# G431.net
KiCad netlist of a schematic drawn in Altium Designer
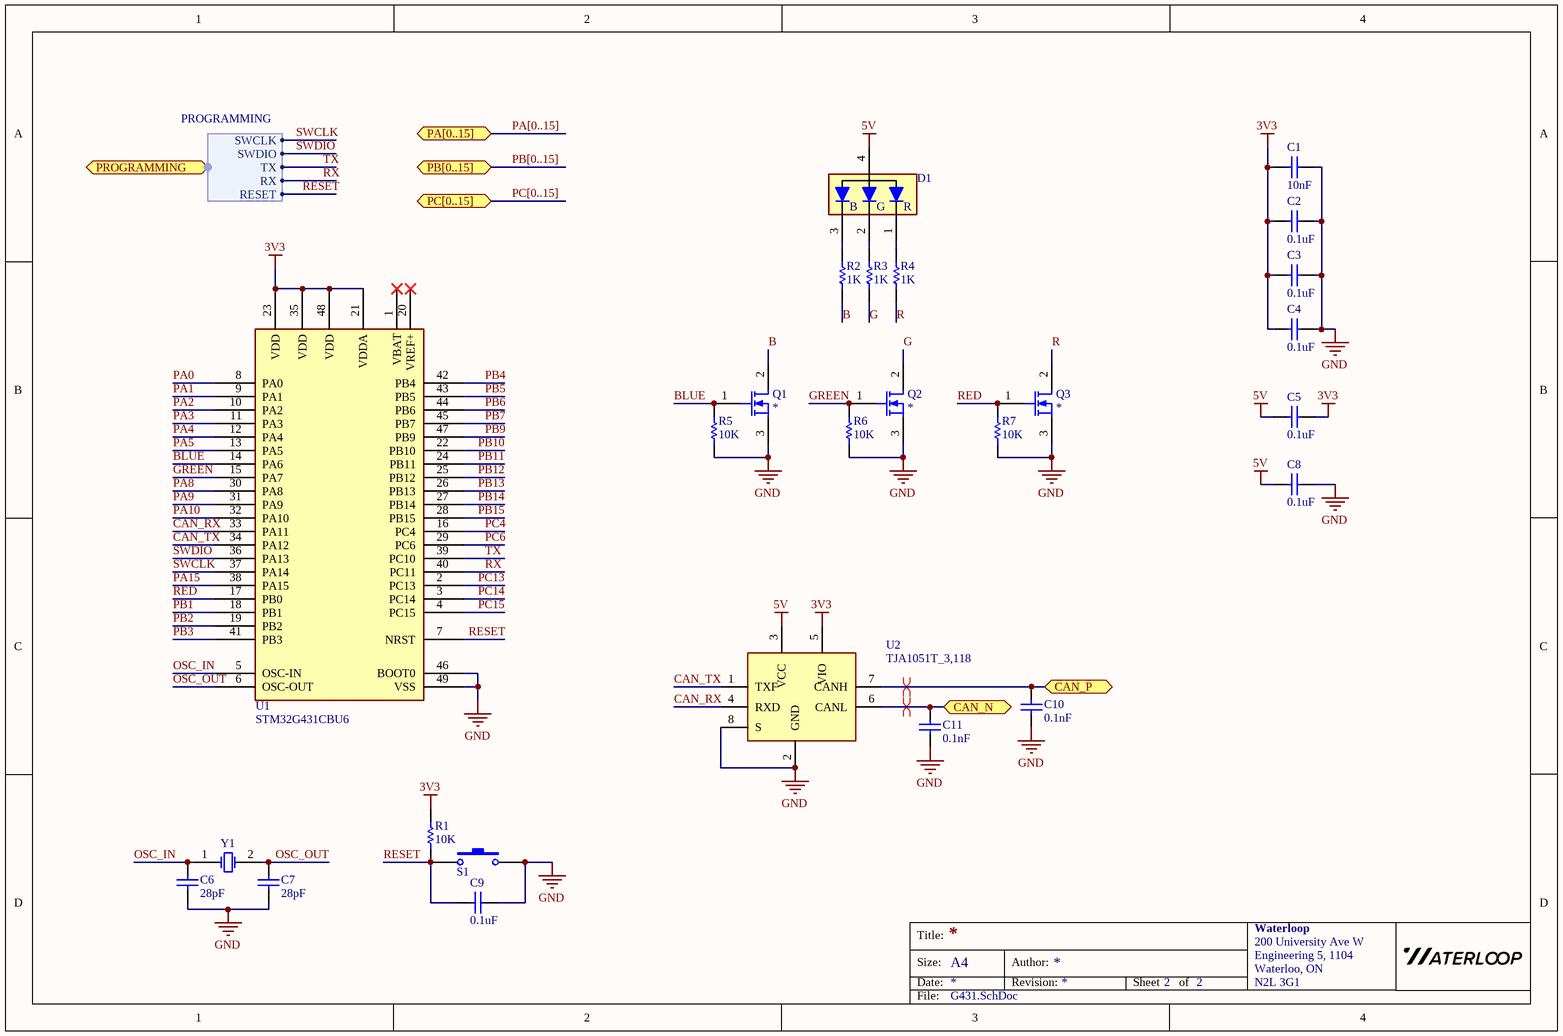
[diagram p0: G431.SchDoc]

(export (version "E")
  (design (tool "Eeschema 10.0.6"))
  (components
    (comp (ref "C1")
      (value "10nF")
      (footprint "0805 - Capacitor")
      (description "Nonpolarized Capacitor")
      (fields (field (name "Comment") "Capacitor - Nonpolarized"))
      (libsource (lib "General") (part "Capacitor - Nonpolarized"))
    )
    (comp (ref "C2")
      (value "0.1uF")
      (footprint "0805 - Capacitor")
      (description "Nonpolarized Capacitor")
      (fields (field (name "Comment") "Capacitor - Nonpolarized"))
      (libsource (lib "General") (part "Capacitor - Nonpolarized"))
    )
    (comp (ref "C3")
      (value "0.1uF")
      (footprint "0805 - Capacitor")
      (description "Nonpolarized Capacitor")
      (fields (field (name "Comment") "Capacitor - Nonpolarized"))
      (libsource (lib "General") (part "Capacitor - Nonpolarized"))
    )
    (comp (ref "C4")
      (value "0.1uF")
      (footprint "0805 - Capacitor")
      (description "Nonpolarized Capacitor")
      (fields (field (name "Comment") "Capacitor - Nonpolarized"))
      (libsource (lib "General") (part "Capacitor - Nonpolarized"))
    )
    (comp (ref "C5")
      (value "0.1uF")
      (footprint "0805 - Capacitor")
      (description "Nonpolarized Capacitor")
      (fields (field (name "Comment") "Capacitor - Nonpolarized"))
      (libsource (lib "General") (part "Capacitor - Nonpolarized"))
    )
    (comp (ref "C6")
      (value "28pF")
      (footprint "0805 - Capacitor")
      (description "Nonpolarized Capacitor")
      (fields (field (name "Comment") "Capacitor - Nonpolarized"))
      (libsource (lib "General") (part "Capacitor - Nonpolarized"))
    )
    (comp (ref "C7")
      (value "28pF")
      (footprint "0805 - Capacitor")
      (description "Nonpolarized Capacitor")
      (fields (field (name "Comment") "Capacitor - Nonpolarized"))
      (libsource (lib "General") (part "Capacitor - Nonpolarized"))
    )
    (comp (ref "C8")
      (value "0.1uF")
      (footprint "0805 - Capacitor")
      (description "Nonpolarized Capacitor")
      (fields (field (name "Comment") "Capacitor - Nonpolarized"))
      (libsource (lib "General") (part "Capacitor - Nonpolarized"))
    )
    (comp (ref "C9")
      (value "0.1uF")
      (footprint "0805 - Capacitor")
      (description "Nonpolarized Capacitor")
      (fields (field (name "Comment") "Capacitor - Nonpolarized"))
      (libsource (lib "General") (part "Capacitor - Nonpolarized"))
    )
    (comp (ref "C10")
      (value "0.1nF")
      (footprint "0805 - Capacitor")
      (description "Nonpolarized Capacitor")
      (fields (field (name "Comment") "Capacitor - Nonpolarized"))
      (libsource (lib "General") (part "Capacitor - Nonpolarized"))
    )
    (comp (ref "C11")
      (value "0.1nF")
      (footprint "0805 - Capacitor")
      (description "Nonpolarized Capacitor")
      (fields (field (name "Comment") "Capacitor - Nonpolarized"))
      (libsource (lib "General") (part "Capacitor - Nonpolarized"))
    )
    (comp (ref "D1")
      (value "RGB LED- Common Anode")
      (footprint "4-PLCC RGB LED")
      (libsource (lib "General") (part "RGB LED- Common Anode"))
    )
    (comp (ref "Q1")
      (value "MOSFET-N")
      (footprint "SC70/SOT323")
      (description "N-Channel MOSFET")
      (fields (field (name "ALTIUM_VALUE") "*"))
      (libsource (lib "General") (part "MOSFET-N"))
    )
    (comp (ref "Q2")
      (value "MOSFET-N")
      (footprint "SC70/SOT323")
      (description "N-Channel MOSFET")
      (fields (field (name "ALTIUM_VALUE") "*"))
      (libsource (lib "General") (part "MOSFET-N"))
    )
    (comp (ref "Q3")
      (value "MOSFET-N")
      (footprint "SC70/SOT323")
      (description "N-Channel MOSFET")
      (fields (field (name "ALTIUM_VALUE") "*"))
      (libsource (lib "General") (part "MOSFET-N"))
    )
    (comp (ref "R1")
      (value "10K")
      (footprint "0603 - Resistor")
      (description "Resistor")
      (libsource (lib "General") (part "Resistor"))
    )
    (comp (ref "R2")
      (value "1K")
      (footprint "0603 - Resistor")
      (description "Resistor")
      (libsource (lib "General") (part "Resistor"))
    )
    (comp (ref "R3")
      (value "1K")
      (footprint "0603 - Resistor")
      (description "Resistor")
      (libsource (lib "General") (part "Resistor"))
    )
    (comp (ref "R4")
      (value "1K")
      (footprint "0603 - Resistor")
      (description "Resistor")
      (libsource (lib "General") (part "Resistor"))
    )
    (comp (ref "R5")
      (value "10K")
      (footprint "0603 - Resistor")
      (description "Resistor")
      (libsource (lib "General") (part "Resistor"))
    )
    (comp (ref "R6")
      (value "10K")
      (footprint "0603 - Resistor")
      (description "Resistor")
      (libsource (lib "General") (part "Resistor"))
    )
    (comp (ref "R7")
      (value "10K")
      (footprint "0603 - Resistor")
      (description "Resistor")
      (libsource (lib "General") (part "Resistor"))
    )
    (comp (ref "S1")
      (value "Switch - Push Button")
      (footprint "6x6mm Switch")
      (description "Push Button Switch")
      (libsource (lib "General") (part "Switch - Push Button"))
    )
    (comp (ref "U1")
      (value "STM32G431CBU6")
      (footprint "STM32G431CBU6")
      (description "128K FLASH + 32K RAM MICRO")
      (fields (field (name "MANUFACTURER") "ST"))
      (libsource (lib "GeneralComponents") (part "STM32G431CBU6"))
    )
    (comp (ref "U2")
      (value "TJA1051T_3,118")
      (footprint "TJA1051T/3,118")
      (description "CAN Transceiver IC 4.5V-5.5V 250ns")
      (fields (field (name "MANUFACTURER") "NXP") (field (name "MANUFACTURER PART NUMBER") "TJA1051T/3,118"))
      (libsource (lib "GeneralComponents") (part "TJA1051T_3,118"))
    )
    (comp (ref "Y1")
      (value "Oscillator")
      (footprint "2-SMD NO LEAD CRSYSTAL")
      (description "Crystal Oscillator")
      (libsource (lib "General") (part "Oscillator"))
    )
  )
  (nets
    (net (code "21") (name "/B") (class "Default")
      (node (ref "Q1") (pin "2") (pinfunction "D_2") (pintype "passive"))
      (node (ref "R2") (pin "1") (pinfunction "1_1") (pintype "passive"))
    )
    (net (code "22") (name "/BLUE") (class "Default")
      (node (ref "Q1") (pin "1") (pinfunction "G_1") (pintype "passive"))
      (node (ref "R5") (pin "2") (pinfunction "2_2") (pintype "passive"))
      (node (ref "U1") (pin "14") (pinfunction "PA6_14") (pintype "passive"))
    )
    (net (code "23") (name "/CAN_N") (class "Default")
      (node (ref "C11") (pin "2") (pinfunction "2_2") (pintype "passive"))
      (node (ref "U2") (pin "6") (pinfunction "CANL_6") (pintype "passive"))
    )
    (net (code "24") (name "/CAN_P") (class "Default")
      (node (ref "C10") (pin "2") (pinfunction "2_2") (pintype "passive"))
      (node (ref "U2") (pin "7") (pinfunction "CANH_7") (pintype "passive"))
    )
    (net (code "25") (name "/CAN_RX") (class "Default")
      (node (ref "U1") (pin "33") (pinfunction "PA11_33") (pintype "passive"))
      (node (ref "U2") (pin "4") (pinfunction "RXD_4") (pintype "passive"))
    )
    (net (code "26") (name "/CAN_TX") (class "Default")
      (node (ref "U1") (pin "34") (pinfunction "PA12_34") (pintype "passive"))
      (node (ref "U2") (pin "1") (pinfunction "TXF_1") (pintype "passive"))
    )
    (net (code "27") (name "/G") (class "Default")
      (node (ref "Q2") (pin "2") (pinfunction "D_2") (pintype "passive"))
      (node (ref "R3") (pin "1") (pinfunction "1_1") (pintype "passive"))
    )
    (net (code "28") (name "/GREEN") (class "Default")
      (node (ref "Q2") (pin "1") (pinfunction "G_1") (pintype "passive"))
      (node (ref "R6") (pin "2") (pinfunction "2_2") (pintype "passive"))
      (node (ref "U1") (pin "15") (pinfunction "PA7_15") (pintype "passive"))
    )
    (net (code "29") (name "/OSC_IN") (class "Default")
      (node (ref "C6") (pin "2") (pinfunction "2_2") (pintype "passive"))
      (node (ref "U1") (pin "5") (pinfunction "OSC-IN_5") (pintype "passive"))
      (node (ref "Y1") (pin "1") (pinfunction "OSC1_1") (pintype "passive"))
    )
    (net (code "30") (name "/OSC_OUT") (class "Default")
      (node (ref "C7") (pin "2") (pinfunction "2_2") (pintype "passive"))
      (node (ref "U1") (pin "6") (pinfunction "OSC-OUT_6") (pintype "passive"))
      (node (ref "Y1") (pin "2") (pinfunction "OSC2_2") (pintype "passive"))
    )
    (net (code "31") (name "/PA0") (class "Default")
      (node (ref "U1") (pin "8") (pinfunction "PA0_8") (pintype "passive"))
    )
    (net (code "32") (name "/PA1") (class "Default")
      (node (ref "U1") (pin "9") (pinfunction "PA1_9") (pintype "passive"))
    )
    (net (code "33") (name "/PA2") (class "Default")
      (node (ref "U1") (pin "10") (pinfunction "PA2_10") (pintype "passive"))
    )
    (net (code "34") (name "/PA3") (class "Default")
      (node (ref "U1") (pin "11") (pinfunction "PA3_11") (pintype "passive"))
    )
    (net (code "35") (name "/PA4") (class "Default")
      (node (ref "U1") (pin "12") (pinfunction "PA4_12") (pintype "passive"))
    )
    (net (code "36") (name "/PA5") (class "Default")
      (node (ref "U1") (pin "13") (pinfunction "PA5_13") (pintype "passive"))
    )
    (net (code "37") (name "/PA8") (class "Default")
      (node (ref "U1") (pin "30") (pinfunction "PA8_30") (pintype "passive"))
    )
    (net (code "38") (name "/PA9") (class "Default")
      (node (ref "U1") (pin "31") (pinfunction "PA9_31") (pintype "passive"))
    )
    (net (code "39") (name "/PA10") (class "Default")
      (node (ref "U1") (pin "32") (pinfunction "PA10_32") (pintype "passive"))
    )
    (net (code "40") (name "/PA15") (class "Default")
      (node (ref "U1") (pin "38") (pinfunction "PA15_38") (pintype "passive"))
    )
    (net (code "42") (name "/PB1") (class "Default")
      (node (ref "U1") (pin "18") (pinfunction "PB1_18") (pintype "passive"))
    )
    (net (code "43") (name "/PB2") (class "Default")
      (node (ref "U1") (pin "19") (pinfunction "PB2_19") (pintype "passive"))
    )
    (net (code "44") (name "/PB3") (class "Default")
      (node (ref "U1") (pin "41") (pinfunction "PB3_41") (pintype "passive"))
    )
    (net (code "45") (name "/PB4") (class "Default")
      (node (ref "U1") (pin "42") (pinfunction "PB4_42") (pintype "passive"))
    )
    (net (code "46") (name "/PB5") (class "Default")
      (node (ref "U1") (pin "43") (pinfunction "PB5_43") (pintype "passive"))
    )
    (net (code "47") (name "/PB6") (class "Default")
      (node (ref "U1") (pin "44") (pinfunction "PB6_44") (pintype "passive"))
    )
    (net (code "48") (name "/PB7") (class "Default")
      (node (ref "U1") (pin "45") (pinfunction "PB7_45") (pintype "passive"))
    )
    (net (code "49") (name "/PB9") (class "Default")
      (node (ref "U1") (pin "47") (pinfunction "PB9_47") (pintype "passive"))
    )
    (net (code "50") (name "/PB10") (class "Default")
      (node (ref "U1") (pin "22") (pinfunction "PB10_22") (pintype "passive"))
    )
    (net (code "51") (name "/PB11") (class "Default")
      (node (ref "U1") (pin "24") (pinfunction "PB11_24") (pintype "passive"))
    )
    (net (code "52") (name "/PB12") (class "Default")
      (node (ref "U1") (pin "25") (pinfunction "PB12_25") (pintype "passive"))
    )
    (net (code "53") (name "/PB13") (class "Default")
      (node (ref "U1") (pin "26") (pinfunction "PB13_26") (pintype "passive"))
    )
    (net (code "54") (name "/PB14") (class "Default")
      (node (ref "U1") (pin "27") (pinfunction "PB14_27") (pintype "passive"))
    )
    (net (code "55") (name "/PB15") (class "Default")
      (node (ref "U1") (pin "28") (pinfunction "PB15_28") (pintype "passive"))
    )
    (net (code "57") (name "/PC4") (class "Default")
      (node (ref "U1") (pin "16") (pinfunction "PC4_16") (pintype "passive"))
    )
    (net (code "58") (name "/PC6") (class "Default")
      (node (ref "U1") (pin "29") (pinfunction "PC6_29") (pintype "passive"))
    )
    (net (code "59") (name "/PC13") (class "Default")
      (node (ref "U1") (pin "2") (pinfunction "PC13_2") (pintype "passive"))
    )
    (net (code "60") (name "/PC14") (class "Default")
      (node (ref "U1") (pin "3") (pinfunction "PC14_3") (pintype "passive"))
    )
    (net (code "61") (name "/PC15") (class "Default")
      (node (ref "U1") (pin "4") (pinfunction "PC15_4") (pintype "passive"))
    )
    (net (code "63") (name "/R") (class "Default")
      (node (ref "Q3") (pin "2") (pinfunction "D_2") (pintype "passive"))
      (node (ref "R4") (pin "1") (pinfunction "1_1") (pintype "passive"))
    )
    (net (code "64") (name "/RED") (class "Default")
      (node (ref "Q3") (pin "1") (pinfunction "G_1") (pintype "passive"))
      (node (ref "R7") (pin "2") (pinfunction "2_2") (pintype "passive"))
      (node (ref "U1") (pin "17") (pinfunction "PB0_17") (pintype "passive"))
    )
    (net (code "65") (name "/RESET") (class "Default")
      (node (ref "C9") (pin "1") (pinfunction "1_1") (pintype "passive"))
      (node (ref "R1") (pin "1") (pinfunction "1_1") (pintype "passive"))
      (node (ref "S1") (pin "1") (pinfunction "1_1") (pintype "passive"))
      (node (ref "U1") (pin "7") (pinfunction "NRST_7") (pintype "passive"))
    )
    (net (code "66") (name "/RX") (class "Default")
      (node (ref "U1") (pin "40") (pinfunction "PC11_40") (pintype "passive"))
    )
    (net (code "67") (name "/SWCLK") (class "Default")
      (node (ref "U1") (pin "37") (pinfunction "PA14_37") (pintype "passive"))
    )
    (net (code "68") (name "/SWDIO") (class "Default")
      (node (ref "U1") (pin "36") (pinfunction "PA13_36") (pintype "passive"))
    )
    (net (code "69") (name "/TX") (class "Default")
      (node (ref "U1") (pin "39") (pinfunction "PC10_39") (pintype "passive"))
    )
    (net (code "71") (name "3V3") (class "Default")
      (node (ref "C1") (pin "1") (pinfunction "1_1") (pintype "passive"))
      (node (ref "C2") (pin "1") (pinfunction "1_1") (pintype "passive"))
      (node (ref "C3") (pin "1") (pinfunction "1_1") (pintype "passive"))
      (node (ref "C4") (pin "1") (pinfunction "1_1") (pintype "passive"))
      (node (ref "C5") (pin "2") (pinfunction "2_2") (pintype "passive"))
      (node (ref "R1") (pin "2") (pinfunction "2_2") (pintype "passive"))
      (node (ref "U1") (pin "21") (pinfunction "VDDA_21") (pintype "passive"))
      (node (ref "U1") (pin "23") (pinfunction "VDD_23") (pintype "passive"))
      (node (ref "U1") (pin "35") (pinfunction "VDD_35") (pintype "passive"))
      (node (ref "U1") (pin "48") (pinfunction "VDD_48") (pintype "passive"))
      (node (ref "U2") (pin "5") (pinfunction "VIO_5") (pintype "passive"))
    )
    (net (code "72") (name "5V") (class "Default")
      (node (ref "C5") (pin "1") (pinfunction "1_1") (pintype "passive"))
      (node (ref "C8") (pin "1") (pinfunction "1_1") (pintype "passive"))
      (node (ref "D1") (pin "4") (pinfunction "11_4") (pintype "passive"))
      (node (ref "U2") (pin "3") (pinfunction "VCC_3") (pintype "passive"))
    )
    (net (code "73") (name "GND") (class "Default")
      (node (ref "C1") (pin "2") (pinfunction "2_2") (pintype "passive"))
      (node (ref "C10") (pin "1") (pinfunction "1_1") (pintype "passive"))
      (node (ref "C11") (pin "1") (pinfunction "1_1") (pintype "passive"))
      (node (ref "C2") (pin "2") (pinfunction "2_2") (pintype "passive"))
      (node (ref "C3") (pin "2") (pinfunction "2_2") (pintype "passive"))
      (node (ref "C4") (pin "2") (pinfunction "2_2") (pintype "passive"))
      (node (ref "C6") (pin "1") (pinfunction "1_1") (pintype "passive"))
      (node (ref "C7") (pin "1") (pinfunction "1_1") (pintype "passive"))
      (node (ref "C8") (pin "2") (pinfunction "2_2") (pintype "passive"))
      (node (ref "C9") (pin "2") (pinfunction "2_2") (pintype "passive"))
      (node (ref "Q1") (pin "3") (pinfunction "S_3") (pintype "passive"))
      (node (ref "Q2") (pin "3") (pinfunction "S_3") (pintype "passive"))
      (node (ref "Q3") (pin "3") (pinfunction "S_3") (pintype "passive"))
      (node (ref "R5") (pin "1") (pinfunction "1_1") (pintype "passive"))
      (node (ref "R6") (pin "1") (pinfunction "1_1") (pintype "passive"))
      (node (ref "R7") (pin "1") (pinfunction "1_1") (pintype "passive"))
      (node (ref "S1") (pin "2") (pinfunction "2_2") (pintype "passive"))
      (node (ref "U1") (pin "46") (pinfunction "BOOT0_46") (pintype "passive"))
      (node (ref "U1") (pin "49") (pinfunction "VSS_49") (pintype "passive"))
      (node (ref "U2") (pin "2") (pinfunction "GND_2") (pintype "passive"))
      (node (ref "U2") (pin "8") (pinfunction "S_8") (pintype "passive"))
    )
    (net (code "74") (name "Net-(D1-11-Pad1)") (class "Default")
      (node (ref "D1") (pin "1") (pinfunction "11_1") (pintype "passive"))
      (node (ref "R4") (pin "2") (pinfunction "2_2") (pintype "passive"))
    )
    (net (code "75") (name "Net-(D1-11-Pad2)") (class "Default")
      (node (ref "D1") (pin "2") (pinfunction "11_2") (pintype "passive"))
      (node (ref "R3") (pin "2") (pinfunction "2_2") (pintype "passive"))
    )
    (net (code "76") (name "Net-(D1-11-Pad3)") (class "Default")
      (node (ref "D1") (pin "3") (pinfunction "11_3") (pintype "passive"))
      (node (ref "R2") (pin "2") (pinfunction "2_2") (pintype "passive"))
    )
    (net (code "77") (name "unconnected-(U1-VBAT-Pad1)") (class "Default")
      (node (ref "U1") (pin "1") (pinfunction "VBAT_1") (pintype "passive+no_connect"))
    )
    (net (code "78") (name "unconnected-(U1-VREF+-Pad20)") (class "Default")
      (node (ref "U1") (pin "20") (pinfunction "VREF+_20") (pintype "passive+no_connect"))
    )
  )
)
